# Gate_to_Trig_Converter_V1.net
KiCad netlist of a schematic drawn in EAGLE
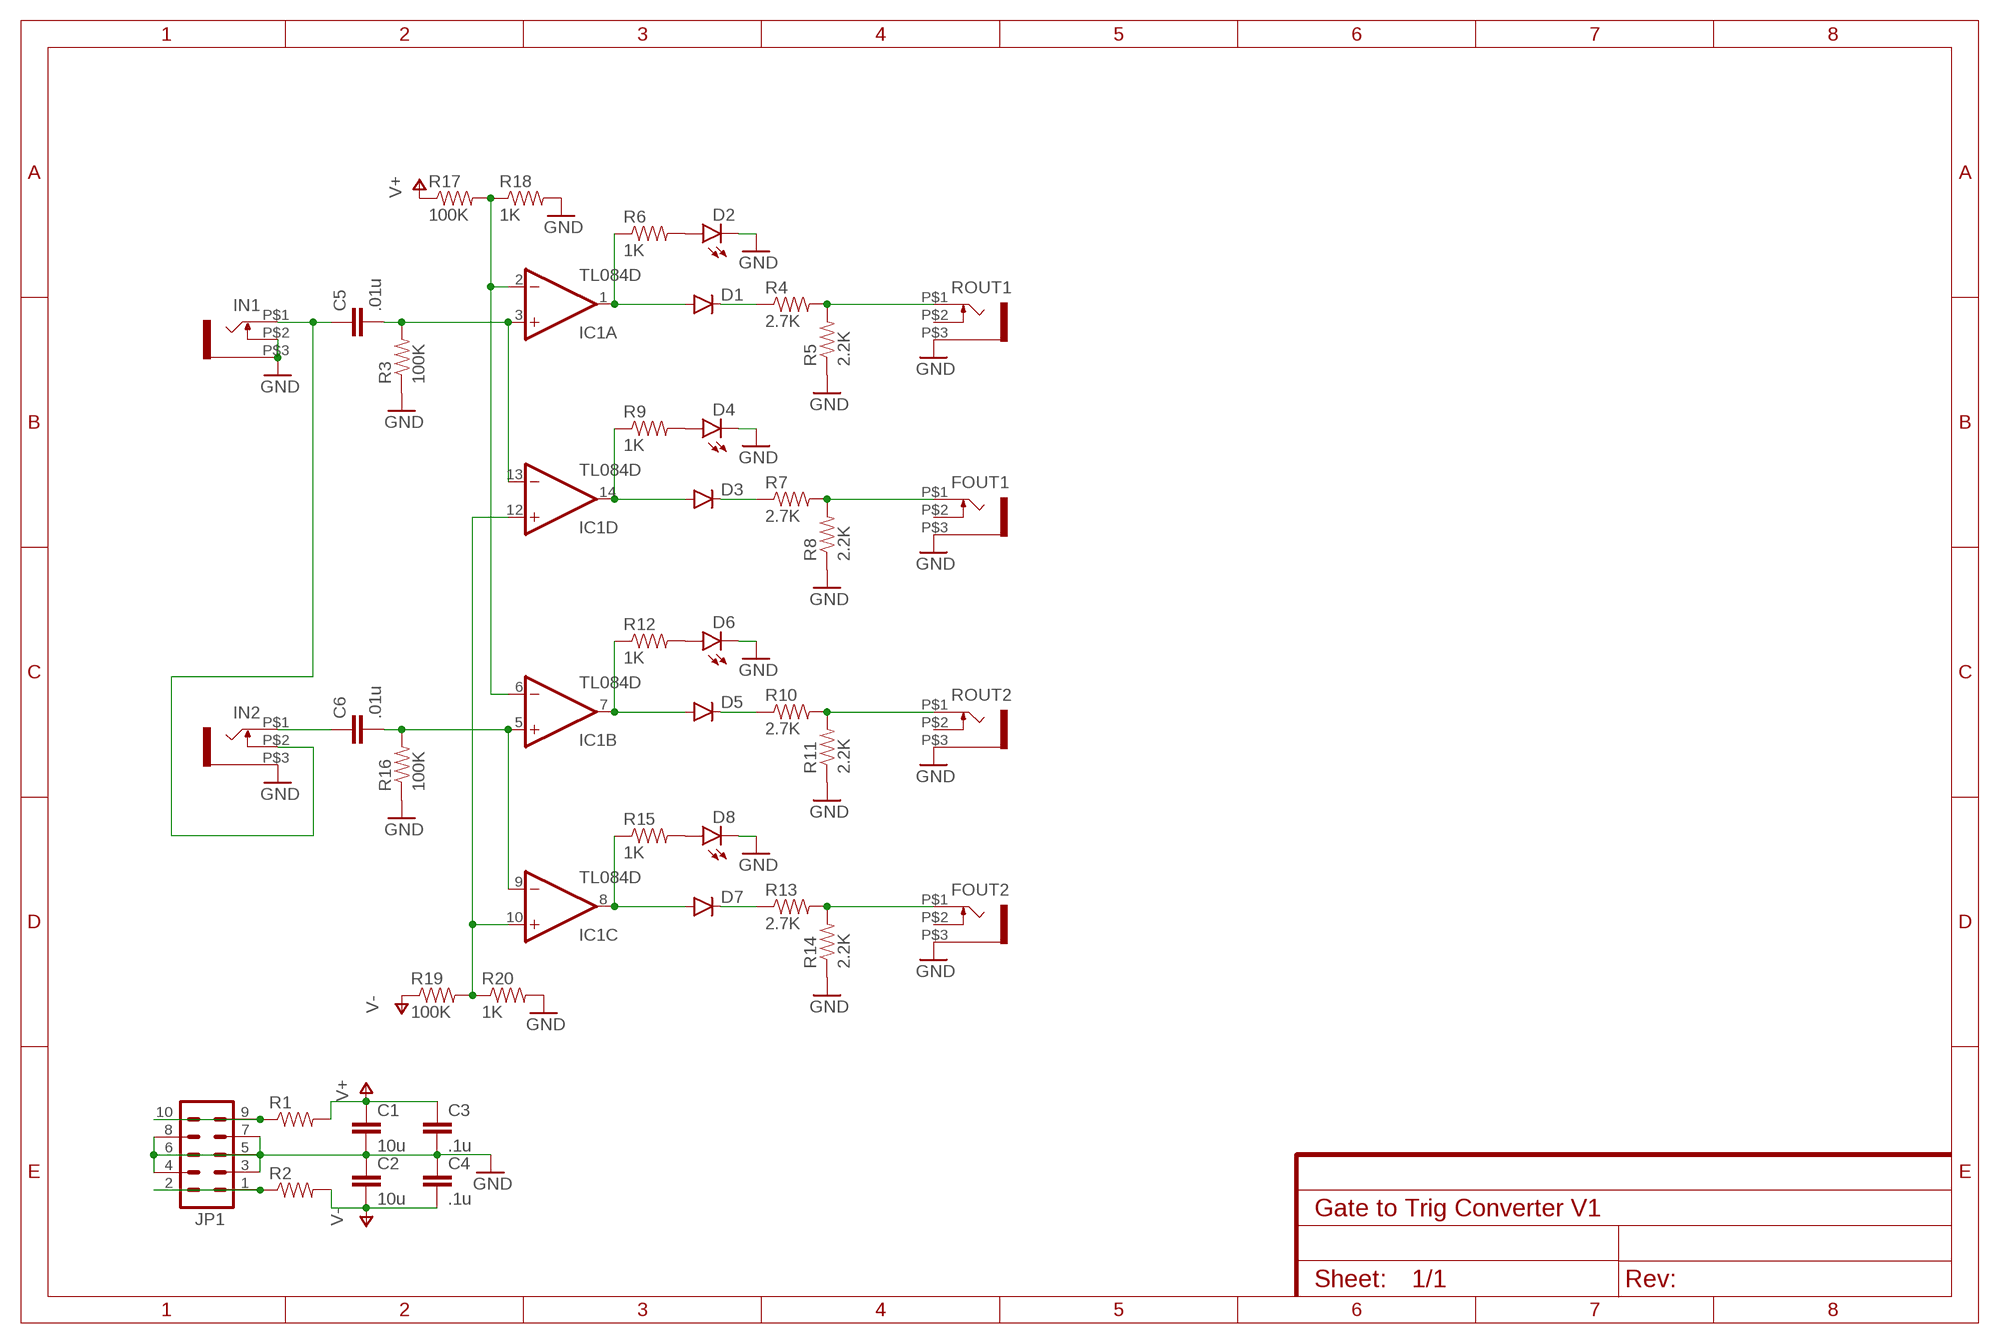
[diagram p0: schematic, sheet 1]

(export (version "E")
  (design (tool "Eeschema 10.0.6"))
  (components
    (comp (ref "C1")
      (value "10u")
      (footprint "eagle-import:1206")
      (libsource (lib "eagle-import") (part "CAP1206"))
    )
    (comp (ref "C2")
      (value "10u")
      (footprint "eagle-import:1206")
      (libsource (lib "eagle-import") (part "CAP1206"))
    )
    (comp (ref "C3")
      (value ".1u")
      (footprint "eagle-import:0805")
      (libsource (lib "eagle-import") (part "CAP0805"))
    )
    (comp (ref "C4")
      (value ".1u")
      (footprint "eagle-import:0805")
      (libsource (lib "eagle-import") (part "CAP0805"))
    )
    (comp (ref "C5")
      (value ".01u")
      (footprint "eagle-import:0805")
      (libsource (lib "eagle-import") (part "CAP0805"))
    )
    (comp (ref "C6")
      (value ".01u")
      (footprint "eagle-import:0805")
      (libsource (lib "eagle-import") (part "CAP0805"))
    )
    (comp (ref "D1")
      (value "DIODESOD123")
      (footprint "eagle-import:SOD-123")
      (libsource (lib "eagle-import") (part "DIODESOD123"))
    )
    (comp (ref "D2")
      (value "LED3MM")
      (footprint "eagle-import:LED3MM")
      (libsource (lib "eagle-import") (part "LED3MM"))
    )
    (comp (ref "D3")
      (value "DIODESOD123")
      (footprint "eagle-import:SOD-123")
      (libsource (lib "eagle-import") (part "DIODESOD123"))
    )
    (comp (ref "D4")
      (value "LED3MM")
      (footprint "eagle-import:LED3MM")
      (libsource (lib "eagle-import") (part "LED3MM"))
    )
    (comp (ref "D5")
      (value "DIODESOD123")
      (footprint "eagle-import:SOD-123")
      (libsource (lib "eagle-import") (part "DIODESOD123"))
    )
    (comp (ref "D6")
      (value "LED3MM")
      (footprint "eagle-import:LED3MM")
      (libsource (lib "eagle-import") (part "LED3MM"))
    )
    (comp (ref "D7")
      (value "DIODESOD123")
      (footprint "eagle-import:SOD-123")
      (libsource (lib "eagle-import") (part "DIODESOD123"))
    )
    (comp (ref "D8")
      (value "LED3MM")
      (footprint "eagle-import:LED3MM")
      (libsource (lib "eagle-import") (part "LED3MM"))
    )
    (comp (ref "FOUT1")
      (value "WQP-PJ301M-12_JACK")
      (footprint "eagle-import:WQP-PJ301M-12_JACK")
      (libsource (lib "eagle-import") (part "WQP-PJ301M-12_JACK"))
    )
    (comp (ref "FOUT2")
      (value "WQP-PJ301M-12_JACK")
      (footprint "eagle-import:WQP-PJ301M-12_JACK")
      (libsource (lib "eagle-import") (part "WQP-PJ301M-12_JACK"))
    )
    (comp (ref "IC1")
      (value "TL084D")
      (footprint "eagle-import:SO14")
      (libsource (lib "eagle-import") (part "TL084D"))
    )
    (comp (ref "IN1")
      (value "WQP-PJ301M-12_JACK")
      (footprint "eagle-import:WQP-PJ301M-12_JACK")
      (libsource (lib "eagle-import") (part "WQP-PJ301M-12_JACK"))
    )
    (comp (ref "IN2")
      (value "WQP-PJ301M-12_JACK")
      (footprint "eagle-import:WQP-PJ301M-12_JACK")
      (libsource (lib "eagle-import") (part "WQP-PJ301M-12_JACK"))
    )
    (comp (ref "JP1")
      (value "M05X2PTH")
      (footprint "eagle-import:AVR_ICSP")
      (libsource (lib "eagle-import") (part "M05X2PTH"))
    )
    (comp (ref "R1")
      (value "RESISTOR0805-RES")
      (footprint "eagle-import:0805")
      (libsource (lib "eagle-import") (part "RESISTOR0805-RES"))
    )
    (comp (ref "R2")
      (value "RESISTOR0805-RES")
      (footprint "eagle-import:0805")
      (libsource (lib "eagle-import") (part "RESISTOR0805-RES"))
    )
    (comp (ref "R3")
      (value "100K")
      (footprint "eagle-import:0805")
      (libsource (lib "eagle-import") (part "RESISTOR0805-RES"))
    )
    (comp (ref "R4")
      (value "2.7K")
      (footprint "eagle-import:0805")
      (libsource (lib "eagle-import") (part "RESISTOR0805-RES"))
    )
    (comp (ref "R5")
      (value "2.2K")
      (footprint "eagle-import:0805")
      (libsource (lib "eagle-import") (part "RESISTOR0805-RES"))
    )
    (comp (ref "R6")
      (value "1K")
      (footprint "eagle-import:0805")
      (libsource (lib "eagle-import") (part "RESISTOR0805-RES"))
    )
    (comp (ref "R7")
      (value "2.7K")
      (footprint "eagle-import:0805")
      (libsource (lib "eagle-import") (part "RESISTOR0805-RES"))
    )
    (comp (ref "R8")
      (value "2.2K")
      (footprint "eagle-import:0805")
      (libsource (lib "eagle-import") (part "RESISTOR0805-RES"))
    )
    (comp (ref "R9")
      (value "1K")
      (footprint "eagle-import:0805")
      (libsource (lib "eagle-import") (part "RESISTOR0805-RES"))
    )
    (comp (ref "R10")
      (value "2.7K")
      (footprint "eagle-import:0805")
      (libsource (lib "eagle-import") (part "RESISTOR0805-RES"))
    )
    (comp (ref "R11")
      (value "2.2K")
      (footprint "eagle-import:0805")
      (libsource (lib "eagle-import") (part "RESISTOR0805-RES"))
    )
    (comp (ref "R12")
      (value "1K")
      (footprint "eagle-import:0805")
      (libsource (lib "eagle-import") (part "RESISTOR0805-RES"))
    )
    (comp (ref "R13")
      (value "2.7K")
      (footprint "eagle-import:0805")
      (libsource (lib "eagle-import") (part "RESISTOR0805-RES"))
    )
    (comp (ref "R14")
      (value "2.2K")
      (footprint "eagle-import:0805")
      (libsource (lib "eagle-import") (part "RESISTOR0805-RES"))
    )
    (comp (ref "R15")
      (value "1K")
      (footprint "eagle-import:0805")
      (libsource (lib "eagle-import") (part "RESISTOR0805-RES"))
    )
    (comp (ref "R16")
      (value "100K")
      (footprint "eagle-import:0805")
      (libsource (lib "eagle-import") (part "RESISTOR0805-RES"))
    )
    (comp (ref "R17")
      (value "100K")
      (footprint "eagle-import:0805")
      (libsource (lib "eagle-import") (part "RESISTOR0805-RES"))
    )
    (comp (ref "R18")
      (value "1K")
      (footprint "eagle-import:0805")
      (libsource (lib "eagle-import") (part "RESISTOR0805-RES"))
    )
    (comp (ref "R19")
      (value "100K")
      (footprint "eagle-import:0805")
      (libsource (lib "eagle-import") (part "RESISTOR0805-RES"))
    )
    (comp (ref "R20")
      (value "1K")
      (footprint "eagle-import:0805")
      (libsource (lib "eagle-import") (part "RESISTOR0805-RES"))
    )
    (comp (ref "ROUT1")
      (value "WQP-PJ301M-12_JACK")
      (footprint "eagle-import:WQP-PJ301M-12_JACK")
      (libsource (lib "eagle-import") (part "WQP-PJ301M-12_JACK"))
    )
    (comp (ref "ROUT2")
      (value "WQP-PJ301M-12_JACK")
      (footprint "eagle-import:WQP-PJ301M-12_JACK")
      (libsource (lib "eagle-import") (part "WQP-PJ301M-12_JACK"))
    )
  )
  (nets
    (net (code "1") (name "GND") (class "Default")
      (node (ref "C1") (pin "2") (pinfunction "2_2") (pintype "passive"))
      (node (ref "C2") (pin "1") (pinfunction "1_1") (pintype "passive"))
      (node (ref "C3") (pin "2") (pinfunction "2_2") (pintype "passive"))
      (node (ref "C4") (pin "1") (pinfunction "1_1") (pintype "passive"))
      (node (ref "D2") (pin "K") (pinfunction "C_K") (pintype "passive"))
      (node (ref "D4") (pin "K") (pinfunction "C_K") (pintype "passive"))
      (node (ref "D6") (pin "K") (pinfunction "C_K") (pintype "passive"))
      (node (ref "D8") (pin "K") (pinfunction "C_K") (pintype "passive"))
      (node (ref "FOUT1") (pin "P$3") (pinfunction "1_P$3") (pintype "passive"))
      (node (ref "FOUT2") (pin "P$3") (pinfunction "1_P$3") (pintype "passive"))
      (node (ref "IN1") (pin "P$2") (pinfunction "3_P$2") (pintype "passive"))
      (node (ref "IN1") (pin "P$3") (pinfunction "1_P$3") (pintype "passive"))
      (node (ref "IN2") (pin "P$3") (pinfunction "1_P$3") (pintype "passive"))
      (node (ref "JP1") (pin "3") (pinfunction "3_3") (pintype "passive"))
      (node (ref "JP1") (pin "4") (pinfunction "4_4") (pintype "passive"))
      (node (ref "JP1") (pin "5") (pinfunction "5_5") (pintype "passive"))
      (node (ref "JP1") (pin "6") (pinfunction "6_6") (pintype "passive"))
      (node (ref "JP1") (pin "7") (pinfunction "7_7") (pintype "passive"))
      (node (ref "JP1") (pin "8") (pinfunction "8_8") (pintype "passive"))
      (node (ref "R11") (pin "1") (pinfunction "1_1") (pintype "passive"))
      (node (ref "R14") (pin "1") (pinfunction "1_1") (pintype "passive"))
      (node (ref "R16") (pin "1") (pinfunction "1_1") (pintype "passive"))
      (node (ref "R18") (pin "2") (pinfunction "2_2") (pintype "passive"))
      (node (ref "R20") (pin "2") (pinfunction "2_2") (pintype "passive"))
      (node (ref "R3") (pin "1") (pinfunction "1_1") (pintype "passive"))
      (node (ref "R5") (pin "1") (pinfunction "1_1") (pintype "passive"))
      (node (ref "R8") (pin "1") (pinfunction "1_1") (pintype "passive"))
      (node (ref "ROUT1") (pin "P$3") (pinfunction "1_P$3") (pintype "passive"))
      (node (ref "ROUT2") (pin "P$3") (pinfunction "1_P$3") (pintype "passive"))
    )
    (net (code "2") (name "Net-(D1-PadC)") (class "Default")
      (node (ref "D1") (pin "C") (pinfunction "C_C") (pintype "passive"))
      (node (ref "R4") (pin "1") (pinfunction "1_1") (pintype "passive"))
    )
    (net (code "3") (name "Net-(D2-PadA)") (class "Default")
      (node (ref "D2") (pin "A") (pinfunction "A_A") (pintype "passive"))
      (node (ref "R6") (pin "2") (pinfunction "2_2") (pintype "passive"))
    )
    (net (code "4") (name "Net-(D3-PadC)") (class "Default")
      (node (ref "D3") (pin "C") (pinfunction "C_C") (pintype "passive"))
      (node (ref "R7") (pin "1") (pinfunction "1_1") (pintype "passive"))
    )
    (net (code "5") (name "Net-(D4-PadA)") (class "Default")
      (node (ref "D4") (pin "A") (pinfunction "A_A") (pintype "passive"))
      (node (ref "R9") (pin "2") (pinfunction "2_2") (pintype "passive"))
    )
    (net (code "6") (name "Net-(D5-PadC)") (class "Default")
      (node (ref "D5") (pin "C") (pinfunction "C_C") (pintype "passive"))
      (node (ref "R10") (pin "1") (pinfunction "1_1") (pintype "passive"))
    )
    (net (code "7") (name "Net-(D6-PadA)") (class "Default")
      (node (ref "D6") (pin "A") (pinfunction "A_A") (pintype "passive"))
      (node (ref "R12") (pin "2") (pinfunction "2_2") (pintype "passive"))
    )
    (net (code "8") (name "Net-(D7-PadC)") (class "Default")
      (node (ref "D7") (pin "C") (pinfunction "C_C") (pintype "passive"))
      (node (ref "R13") (pin "1") (pinfunction "1_1") (pintype "passive"))
    )
    (net (code "9") (name "Net-(D8-PadA)") (class "Default")
      (node (ref "D8") (pin "A") (pinfunction "A_A") (pintype "passive"))
      (node (ref "R15") (pin "2") (pinfunction "2_2") (pintype "passive"))
    )
    (net (code "10") (name "Net-(FOUT1-2)") (class "Default")
      (node (ref "FOUT1") (pin "P$1") (pinfunction "2_P$1") (pintype "passive"))
      (node (ref "R7") (pin "2") (pinfunction "2_2") (pintype "passive"))
      (node (ref "R8") (pin "2") (pinfunction "2_2") (pintype "passive"))
    )
    (net (code "11") (name "Net-(FOUT2-2)") (class "Default")
      (node (ref "FOUT2") (pin "P$1") (pinfunction "2_P$1") (pintype "passive"))
      (node (ref "R13") (pin "2") (pinfunction "2_2") (pintype "passive"))
      (node (ref "R14") (pin "2") (pinfunction "2_2") (pintype "passive"))
    )
    (net (code "12") (name "Net-(IC1A-+IN)") (class "Default")
      (node (ref "C5") (pin "2") (pinfunction "2_2") (pintype "passive"))
      (node (ref "IC1") (pin "13") (pinfunction "-IN_13") (pintype "input"))
      (node (ref "IC1") (pin "3") (pinfunction "+IN_3") (pintype "input"))
      (node (ref "R3") (pin "2") (pinfunction "2_2") (pintype "passive"))
    )
    (net (code "13") (name "Net-(IC1A--IN)") (class "Default")
      (node (ref "IC1") (pin "2") (pinfunction "-IN_2") (pintype "input"))
      (node (ref "IC1") (pin "6") (pinfunction "-IN_6") (pintype "input"))
      (node (ref "R17") (pin "2") (pinfunction "2_2") (pintype "passive"))
      (node (ref "R18") (pin "1") (pinfunction "1_1") (pintype "passive"))
    )
    (net (code "14") (name "Net-(IC1A-OUT)") (class "Default")
      (node (ref "D1") (pin "A") (pinfunction "A_A") (pintype "passive"))
      (node (ref "IC1") (pin "1") (pinfunction "OUT_1") (pintype "output"))
      (node (ref "R6") (pin "1") (pinfunction "1_1") (pintype "passive"))
    )
    (net (code "15") (name "Net-(IC1B-+IN)") (class "Default")
      (node (ref "C6") (pin "2") (pinfunction "2_2") (pintype "passive"))
      (node (ref "IC1") (pin "5") (pinfunction "+IN_5") (pintype "input"))
      (node (ref "IC1") (pin "9") (pinfunction "-IN_9") (pintype "input"))
      (node (ref "R16") (pin "2") (pinfunction "2_2") (pintype "passive"))
    )
    (net (code "16") (name "Net-(IC1B-OUT)") (class "Default")
      (node (ref "D5") (pin "A") (pinfunction "A_A") (pintype "passive"))
      (node (ref "IC1") (pin "7") (pinfunction "OUT_7") (pintype "output"))
      (node (ref "R12") (pin "1") (pinfunction "1_1") (pintype "passive"))
    )
    (net (code "17") (name "Net-(IC1C-+IN)") (class "Default")
      (node (ref "IC1") (pin "10") (pinfunction "+IN_10") (pintype "input"))
      (node (ref "IC1") (pin "12") (pinfunction "+IN_12") (pintype "input"))
      (node (ref "R19") (pin "2") (pinfunction "2_2") (pintype "passive"))
      (node (ref "R20") (pin "1") (pinfunction "1_1") (pintype "passive"))
    )
    (net (code "18") (name "Net-(IC1C-OUT)") (class "Default")
      (node (ref "D7") (pin "A") (pinfunction "A_A") (pintype "passive"))
      (node (ref "IC1") (pin "8") (pinfunction "OUT_8") (pintype "output"))
      (node (ref "R15") (pin "1") (pinfunction "1_1") (pintype "passive"))
    )
    (net (code "19") (name "Net-(IC1D-OUT)") (class "Default")
      (node (ref "D3") (pin "A") (pinfunction "A_A") (pintype "passive"))
      (node (ref "IC1") (pin "14") (pinfunction "OUT_14") (pintype "output"))
      (node (ref "R9") (pin "1") (pinfunction "1_1") (pintype "passive"))
    )
    (net (code "20") (name "Net-(IN1-2)") (class "Default")
      (node (ref "C5") (pin "1") (pinfunction "1_1") (pintype "passive"))
      (node (ref "IN1") (pin "P$1") (pinfunction "2_P$1") (pintype "passive"))
      (node (ref "IN2") (pin "P$2") (pinfunction "3_P$2") (pintype "passive"))
    )
    (net (code "21") (name "Net-(IN2-2)") (class "Default")
      (node (ref "C6") (pin "1") (pinfunction "1_1") (pintype "passive"))
      (node (ref "IN2") (pin "P$1") (pinfunction "2_P$1") (pintype "passive"))
    )
    (net (code "22") (name "Net-(JP1-Pad1)") (class "Default")
      (node (ref "JP1") (pin "1") (pinfunction "1_1") (pintype "passive"))
      (node (ref "JP1") (pin "2") (pinfunction "2_2") (pintype "passive"))
      (node (ref "R2") (pin "1") (pinfunction "1_1") (pintype "passive"))
    )
    (net (code "23") (name "Net-(JP1-Pad10)") (class "Default")
      (node (ref "JP1") (pin "10") (pinfunction "10_10") (pintype "passive"))
      (node (ref "JP1") (pin "9") (pinfunction "9_9") (pintype "passive"))
      (node (ref "R1") (pin "1") (pinfunction "1_1") (pintype "passive"))
    )
    (net (code "24") (name "Net-(ROUT1-2)") (class "Default")
      (node (ref "R4") (pin "2") (pinfunction "2_2") (pintype "passive"))
      (node (ref "R5") (pin "2") (pinfunction "2_2") (pintype "passive"))
      (node (ref "ROUT1") (pin "P$1") (pinfunction "2_P$1") (pintype "passive"))
    )
    (net (code "25") (name "Net-(ROUT2-2)") (class "Default")
      (node (ref "R10") (pin "2") (pinfunction "2_2") (pintype "passive"))
      (node (ref "R11") (pin "2") (pinfunction "2_2") (pintype "passive"))
      (node (ref "ROUT2") (pin "P$1") (pinfunction "2_P$1") (pintype "passive"))
    )
    (net (code "26") (name "V+") (class "Default")
      (node (ref "C1") (pin "1") (pinfunction "1_1") (pintype "passive"))
      (node (ref "C3") (pin "1") (pinfunction "1_1") (pintype "passive"))
      (node (ref "R1") (pin "2") (pinfunction "2_2") (pintype "passive"))
      (node (ref "R17") (pin "1") (pinfunction "1_1") (pintype "passive"))
    )
    (net (code "27") (name "V-") (class "Default")
      (node (ref "C2") (pin "2") (pinfunction "2_2") (pintype "passive"))
      (node (ref "C4") (pin "2") (pinfunction "2_2") (pintype "passive"))
      (node (ref "R19") (pin "1") (pinfunction "1_1") (pintype "passive"))
      (node (ref "R2") (pin "2") (pinfunction "2_2") (pintype "passive"))
    )
    (net (code "28") (name "unconnected-(FOUT1-3-PadP$2)") (class "Default")
      (node (ref "FOUT1") (pin "P$2") (pinfunction "3_P$2") (pintype "passive"))
    )
    (net (code "29") (name "unconnected-(FOUT2-3-PadP$2)") (class "Default")
      (node (ref "FOUT2") (pin "P$2") (pinfunction "3_P$2") (pintype "passive"))
    )
    (net (code "30") (name "unconnected-(ROUT1-3-PadP$2)") (class "Default")
      (node (ref "ROUT1") (pin "P$2") (pinfunction "3_P$2") (pintype "passive"))
    )
    (net (code "31") (name "unconnected-(ROUT2-3-PadP$2)") (class "Default")
      (node (ref "ROUT2") (pin "P$2") (pinfunction "3_P$2") (pintype "passive"))
    )
  )
)
